# POWER.net
KiCad netlist of a schematic drawn in Altium Designer
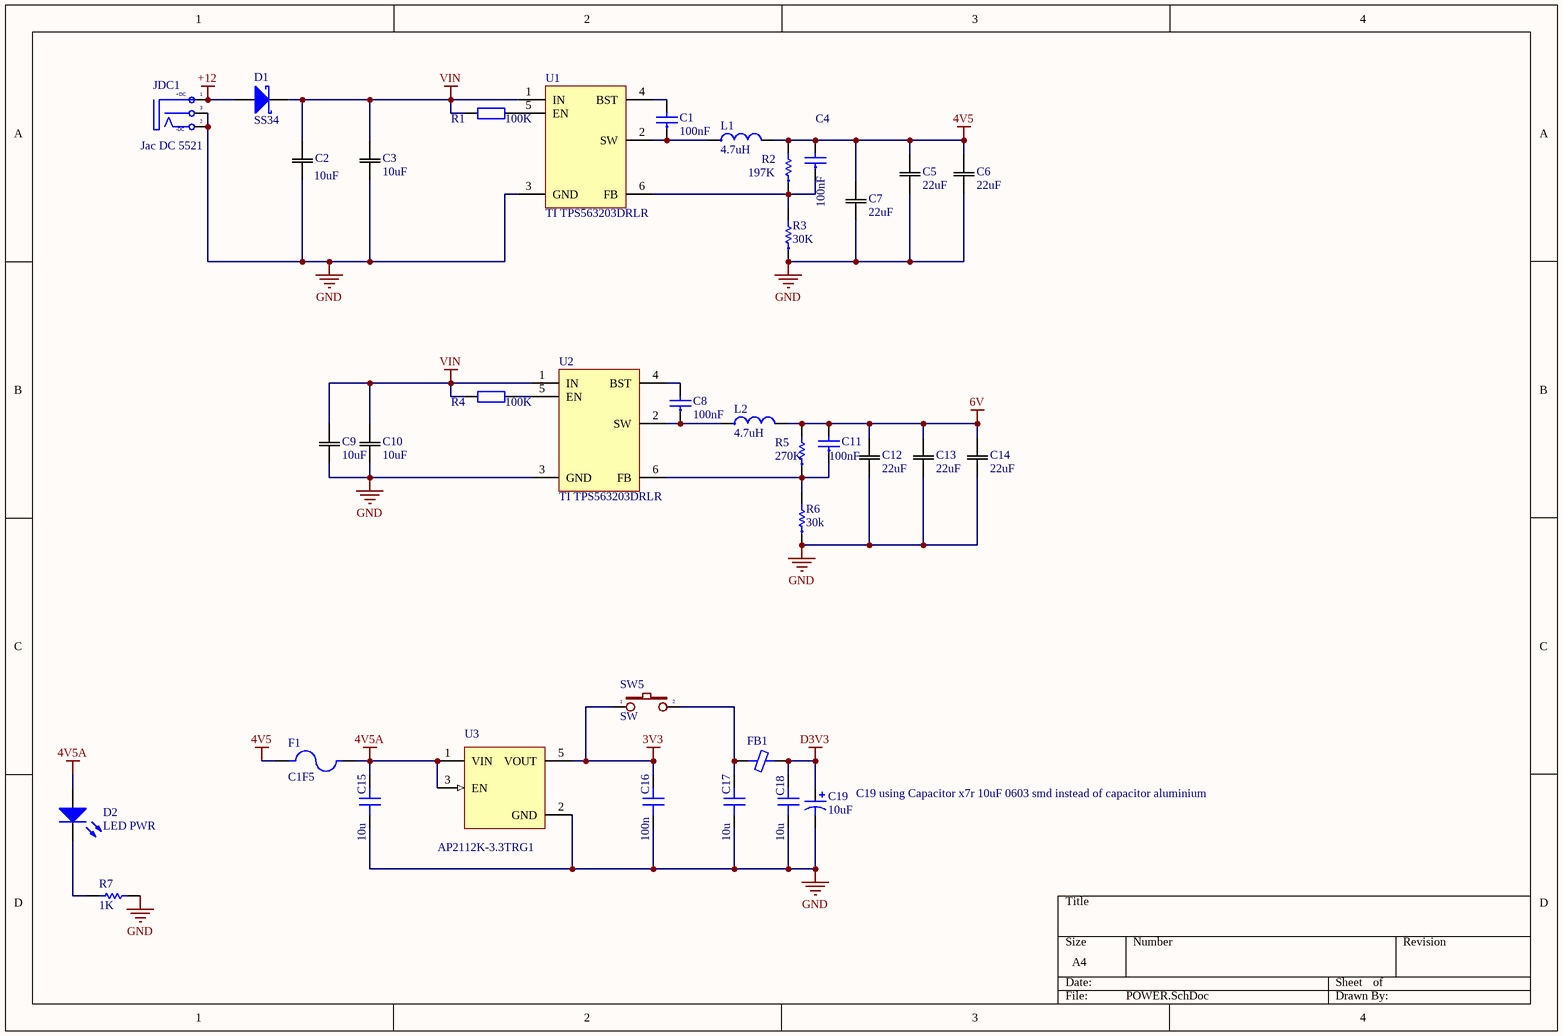
[diagram p0: POWER.SchDoc]

(export (version "E")
  (design (tool "Eeschema 10.0.6"))
  (components
    (comp (ref "C1")
      (value "100nF")
      (footprint "CN-SMD-0603")
      (description "CAP CER 100nF 10% 50V X7R 0603 SMD")
      (libsource (lib "2502-GMQLITE-MAIN") (part "CAPCER0001 100nF 10% 50V X7R 0603 SMD_1"))
    )
    (comp (ref "C2")
      (value "10uF")
      (footprint "CL10A106MQ8NNNC:CAP_CL10_SAM")
      (description "Description")
      (fields
        (field (name "MANUFACTURER_PART_NUMBER") "CL10A106MQ8NNNC")
        (field (name "COPYRIGHT") "Copyright (C) 2026 Ultra Librarian. All rights reserved.")
      )
      (libsource (lib "CL10A106MQ8NNNC") (part "CL10A106MQ8NNNC"))
    )
    (comp (ref "C3")
      (value "10uF")
      (footprint "CL10A106MQ8NNNC:CAP_CL10_SAM")
      (description "Description")
      (fields
        (field (name "MANUFACTURER_PART_NUMBER") "CL10A106MQ8NNNC")
        (field (name "COPYRIGHT") "Copyright (C) 2026 Ultra Librarian. All rights reserved.")
      )
      (libsource (lib "CL10A106MQ8NNNC") (part "CL10A106MQ8NNNC"))
    )
    (comp (ref "C4")
      (value "100nF")
      (footprint "CN-SMD-0603")
      (description "CAP CER 100nF 10% 50V X7R 0603 SMD")
      (libsource (lib "2502-GMQLITE-MAIN") (part "CAPCER0001 100nF 10% 50V X7R 0603 SMD"))
    )
    (comp (ref "C5")
      (value "22uF")
      (footprint "CN-SMD-0603")
      (description "Description")
      (fields
        (field (name "MANUFACTURER_PART_NUMBER") "GRM188R60J226MEA0D")
        (field (name "COPYRIGHT") "Copyright (C) 2026 Ultra Librarian. All rights reserved.")
      )
      (libsource (lib "GRM188R60J226MEA0D") (part "GRM188R60J226MEA0D"))
    )
    (comp (ref "C6")
      (value "22uF")
      (footprint "CN-SMD-0603")
      (description "Description")
      (fields
        (field (name "MANUFACTURER_PART_NUMBER") "GRM188R60J226MEA0D")
        (field (name "COPYRIGHT") "Copyright (C) 2026 Ultra Librarian. All rights reserved.")
      )
      (libsource (lib "GRM188R60J226MEA0D") (part "GRM188R60J226MEA0D"))
    )
    (comp (ref "C7")
      (value "22uF")
      (footprint "CN-SMD-0603")
      (description "Description")
      (fields
        (field (name "MANUFACTURER_PART_NUMBER") "GRM188R60J226MEA0D")
        (field (name "COPYRIGHT") "Copyright (C) 2026 Ultra Librarian. All rights reserved.")
      )
      (libsource (lib "GRM188R60J226MEA0D") (part "GRM188R60J226MEA0D"))
    )
    (comp (ref "C8")
      (value "100nF")
      (footprint "CN-SMD-0603")
      (description "CAP CER 100nF 10% 50V X7R 0603 SMD")
      (libsource (lib "2502-GMQLITE-MAIN") (part "CAPCER0001 100nF 10% 50V X7R 0603 SMD_1"))
    )
    (comp (ref "C9")
      (value "10uF")
      (footprint "CL10A106MQ8NNNC:CAP_CL10_SAM")
      (description "Description")
      (fields
        (field (name "MANUFACTURER_PART_NUMBER") "CL10A106MQ8NNNC")
        (field (name "COPYRIGHT") "Copyright (C) 2026 Ultra Librarian. All rights reserved.")
      )
      (libsource (lib "CL10A106MQ8NNNC") (part "CL10A106MQ8NNNC"))
    )
    (comp (ref "C10")
      (value "10uF")
      (footprint "CL10A106MQ8NNNC:CAP_CL10_SAM")
      (description "Description")
      (fields
        (field (name "MANUFACTURER_PART_NUMBER") "CL10A106MQ8NNNC")
        (field (name "COPYRIGHT") "Copyright (C) 2026 Ultra Librarian. All rights reserved.")
      )
      (libsource (lib "CL10A106MQ8NNNC") (part "CL10A106MQ8NNNC"))
    )
    (comp (ref "C11")
      (value "100nF")
      (footprint "CN-SMD-0603")
      (description "CAP CER 100nF 10% 50V X7R 0603 SMD")
      (libsource (lib "2502-GMQLITE-MAIN") (part "CAPCER0001 100nF 10% 50V X7R 0603 SMD"))
    )
    (comp (ref "C12")
      (value "22uF")
      (footprint "CN-SMD-0603")
      (description "Description")
      (fields
        (field (name "MANUFACTURER_PART_NUMBER") "GRM188R60J226MEA0D")
        (field (name "COPYRIGHT") "Copyright (C) 2026 Ultra Librarian. All rights reserved.")
      )
      (libsource (lib "GRM188R60J226MEA0D") (part "GRM188R60J226MEA0D"))
    )
    (comp (ref "C13")
      (value "22uF")
      (footprint "CN-SMD-0603")
      (description "Description")
      (fields
        (field (name "MANUFACTURER_PART_NUMBER") "GRM188R60J226MEA0D")
        (field (name "COPYRIGHT") "Copyright (C) 2026 Ultra Librarian. All rights reserved.")
      )
      (libsource (lib "GRM188R60J226MEA0D") (part "GRM188R60J226MEA0D"))
    )
    (comp (ref "C14")
      (value "22uF")
      (footprint "CN-SMD-0603")
      (description "Description")
      (fields
        (field (name "MANUFACTURER_PART_NUMBER") "GRM188R60J226MEA0D")
        (field (name "COPYRIGHT") "Copyright (C) 2026 Ultra Librarian. All rights reserved.")
      )
      (libsource (lib "GRM188R60J226MEA0D") (part "GRM188R60J226MEA0D"))
    )
    (comp (ref "C15")
      (value "10u")
      (footprint "CN-SMD-0603")
      (description "CAP0603 X7R 10UF 10% 10V")
      (fields
        (field (name "PART NUMBER") "GMC10X7R106K10NT")
        (field (name "MANUFACTURER") "Cal-Chip Electronics, Inc.")
      )
      (libsource (lib "Celestial Altium Library - altium_library") (part "Capacitor"))
    )
    (comp (ref "C16")
      (value "100n")
      (footprint "CN-SMD-0603")
      (description "CAP0603 X7R 100nF 10% 10V")
      (fields
        (field (name "PART NUMBER") "GMC10X7R106K10NT")
        (field (name "MANUFACTURER") "Cal-Chip Electronics, Inc.")
      )
      (libsource (lib "Celestial Altium Library - altium_library") (part "Capacitor"))
    )
    (comp (ref "C17")
      (value "10u")
      (footprint "CN-SMD-0603")
      (description "CAP0603 X7R 10UF 10% 10V")
      (fields
        (field (name "PART NUMBER") "GMC10X7R106K10NT")
        (field (name "MANUFACTURER") "Cal-Chip Electronics, Inc.")
      )
      (libsource (lib "Celestial Altium Library - altium_library") (part "Capacitor"))
    )
    (comp (ref "C18")
      (value "10u")
      (footprint "CN-SMD-0603")
      (description "CAP0603 X7R 10UF 10% 10V")
      (fields
        (field (name "PART NUMBER") "GMC10X7R106K10NT")
        (field (name "MANUFACTURER") "Cal-Chip Electronics, Inc.")
      )
      (libsource (lib "Celestial Altium Library - altium_library") (part "Capacitor"))
    )
    (comp (ref "C19")
      (value "10uF")
      (footprint "CN-SMD-0603")
      (description "CAP ALUM 100UF 20% \r\n16V SMD")
      (fields (field (name "Comment") "CAP ALUM 100UF 20% 16V SMD"))
      (libsource (lib "capacitor") (part "UWT1C101MCL1GB"))
    )
    (comp (ref "D1")
      (value "SS34")
      (footprint "DIO-SMD-106")
      (description "Schottky Diode 40V 3A SMA")
      (libsource (lib "diode") (part "SS34"))
    )
    (comp (ref "D2")
      (value "LED PWR")
      (footprint "LED-0805-Red")
      (description "Lite-On LED Red 0603")
      (fields (field (name "Comment") "LED Red"))
      (libsource (lib "diode") (part "LTST-C190KRKT"))
    )
    (comp (ref "F1")
      (value "C1F5")
      (footprint "RES-SMD-1206")
      (description "Fuse Chip Fast Acting 5A 125V SMD Solder Pad 1206 3.2 X 1.58 X 0.63mm")
      (fields (field (name "MANUFACTURER") "Bel TRP"))
      (libsource (lib "POWER_PIN_CAMERA") (part "C1F5"))
    )
    (comp (ref "FB1")
      (value "330")
      (footprint "IND_BLM18KG331WH1D_MUR-L")
      (description "FERRITE BEAD 330 OHM 0603 1LN")
      (fields
        (field (name "PART NUMBER") "BLM18KG331SH1D")
        (field (name "MANUFACTURER") "Murata Electronics")
      )
      (libsource (lib "Celestial Altium Library - altium_library") (part "Ferrite Chip"))
    )
    (comp (ref "JDC1")
      (value "Jac DC 5521")
      (footprint "DC0")
      (description "Jac DC input")
      (libsource (lib "2502-GMQLITE-MAIN") (part "DCIN"))
    )
    (comp (ref "L1")
      (value "4.7uH")
      (footprint "Inductor_SMD")
      (description "IND MOI 1W2T 4.7uH 20% 5A 0420 SMD")
      (libsource (lib "2502-GMQLITE-MAIN") (part "INDMOI0016 1W2T 2.2uH 20% 5A 0420 SMD"))
    )
    (comp (ref "L2")
      (value "4.7uH")
      (footprint "Inductor_SMD")
      (description "IND MOI 1W2T 4.7uH 20% 5A 0420 SMD")
      (libsource (lib "2502-GMQLITE-MAIN") (part "INDMOI0016 1W2T 2.2uH 20% 5A 0420 SMD"))
    )
    (comp (ref "R1")
      (value "100K")
      (footprint "RES-SMD-0603")
      (description "Yageo RES 100K 5% 1/10W 0603")
      (fields (field (name "Comment") "RES 100K 5% 1/10W 0603"))
      (libsource (lib "resistor") (part "RC0603JR-07100KL"))
    )
    (comp (ref "R2")
      (value "197K")
      (footprint "RES-SMD-0603")
      (description "RES CHP 2K7 1% 1/10W 0603 SMD")
      (libsource (lib "2502-GMQLITE-MAIN") (part "RESCHP0195 2K7 1% 0603 SMD"))
    )
    (comp (ref "R3")
      (value "30K")
      (footprint "RES-SMD-0603")
      (description "RES CHP 2K7 1% 1/10W 0603 SMD")
      (libsource (lib "2502-GMQLITE-MAIN") (part "RESCHP0195 2K7 1% 0603 SMD"))
    )
    (comp (ref "R4")
      (value "100K")
      (footprint "RES-SMD-0603")
      (description "Yageo RES 100K 5% 1/10W 0603")
      (fields (field (name "Comment") "RES 100K 5% 1/10W 0603"))
      (libsource (lib "resistor") (part "RC0603JR-07100KL"))
    )
    (comp (ref "R5")
      (value "270K")
      (footprint "RES-SMD-0603")
      (description "RES CHP 2K7 1% 1/10W 0603 SMD")
      (libsource (lib "2502-GMQLITE-MAIN") (part "RESCHP0195 2K7 1% 0603 SMD"))
    )
    (comp (ref "R6")
      (value "30k")
      (footprint "RES-SMD-0603")
      (description "RES CHP 2K7 1% 1/10W 0603 SMD")
      (libsource (lib "2502-GMQLITE-MAIN") (part "RESCHP0195 2K7 1% 0603 SMD"))
    )
    (comp (ref "R7")
      (value "1K")
      (footprint "RES-SMD-0603")
      (description "Res Thick Film 0603 2.2K Ohm 5% 1/10W ±200ppm/°C Molded SMD SMD Paper T/R")
      (fields
        (field (name "MANUFACTURER") "Vishay")
        (field (name "MANUFACTURER PART NUMBER") "CRCW06032K20JNEA")
      )
      (libsource (lib "Stm32_Flyback_Driver_250814_1") (part "Resistor 2.2K"))
    )
    (comp (ref "SW5")
      (value "SW")
      (footprint "SW-DIP1")
      (description "Switch button 2 pin")
      (libsource (lib "Altium Library") (part "SW2"))
    )
    (comp (ref "U1")
      (value "TI TPS563203DRLR")
      (footprint "SOT_07SDRLR_TEX")
      (description "ICS OCV BCK TPS563201 3A SOT23-6 SMD")
      (libsource (lib "2502-GMQLITE-MAIN") (part "ICSOCV0021 BCK TPS563201 3A SOT23-6 SMD"))
    )
    (comp (ref "U2")
      (value "TI TPS563203DRLR")
      (footprint "SOT_07SDRLR_TEX")
      (description "ICS OCV BCK TPS563201 3A SOT23-6 SMD")
      (libsource (lib "2502-GMQLITE-MAIN") (part "ICSOCV0021 BCK TPS563201 3A SOT23-6 SMD"))
    )
    (comp (ref "U3")
      (value "AP2112K-3.3TRG1")
      (footprint "AP2112K-3P3TRG1:SOT_RG1_DIO")
      (description "AP2112 Series 0.6 A 3.3 V Fixed Output SMT LDO Linear Regulator - SOT23-5")
      (fields (field (name "MF") "Diodes Inc."))
      (libsource (lib "hanguyen") (part "AP2112K-3.3TRG1"))
    )
  )
  (nets
    (net (code "1") (name "+12") (class "Default")
      (node (ref "D1") (pin "1") (pinfunction "A_1") (pintype "passive"))
      (node (ref "JDC1") (pin "1") (pinfunction "T_1") (pintype "passive"))
    )
    (net (code "2") (name "3V3") (class "Default")
      (node (ref "C16") (pin "2") (pinfunction "2_2") (pintype "passive"))
      (node (ref "SW5") (pin "1") (pinfunction "1_1") (pintype "passive"))
      (node (ref "U3") (pin "5") (pinfunction "VOUT_5") (pintype "power_in"))
    )
    (net (code "3") (name "4V5") (class "Default")
      (node (ref "C4") (pin "2") (pinfunction "2_2") (pintype "passive"))
      (node (ref "C5") (pin "2") (pinfunction "2_2") (pintype "passive"))
      (node (ref "C6") (pin "2") (pinfunction "2_2") (pintype "passive"))
      (node (ref "C7") (pin "2") (pinfunction "2_2") (pintype "passive"))
      (node (ref "F1") (pin "1") (pinfunction "1_1") (pintype "passive"))
      (node (ref "L1") (pin "2") (pinfunction "2_2") (pintype "passive"))
      (node (ref "R2") (pin "2") (pinfunction "2_2") (pintype "passive"))
    )
    (net (code "4") (name "4V5A") (class "Default")
      (node (ref "C15") (pin "2") (pinfunction "2_2") (pintype "passive"))
      (node (ref "D2") (pin "1") (pinfunction "A_1") (pintype "passive"))
      (node (ref "F1") (pin "2") (pinfunction "2_2") (pintype "passive"))
      (node (ref "U3") (pin "1") (pinfunction "VIN_1") (pintype "power_in"))
      (node (ref "U3") (pin "3") (pinfunction "EN_3") (pintype "input"))
    )
    (net (code "5") (name "6V") (class "Default")
      (node (ref "C11") (pin "2") (pinfunction "2_2") (pintype "passive"))
      (node (ref "C12") (pin "2") (pinfunction "2_2") (pintype "passive"))
      (node (ref "C13") (pin "2") (pinfunction "2_2") (pintype "passive"))
      (node (ref "C14") (pin "2") (pinfunction "2_2") (pintype "passive"))
      (node (ref "L2") (pin "2") (pinfunction "2_2") (pintype "passive"))
      (node (ref "R5") (pin "2") (pinfunction "2_2") (pintype "passive"))
    )
    (net (code "6") (name "D3V3") (class "Default")
      (node (ref "C18") (pin "2") (pinfunction "2_2") (pintype "passive"))
      (node (ref "C19") (pin "1") (pinfunction "1_1") (pintype "passive"))
      (node (ref "FB1") (pin "2") (pinfunction "2_2") (pintype "passive"))
    )
    (net (code "7") (name "GND") (class "Default")
      (node (ref "C10") (pin "1") (pinfunction "1_1") (pintype "passive"))
      (node (ref "C12") (pin "1") (pinfunction "1_1") (pintype "passive"))
      (node (ref "C13") (pin "1") (pinfunction "1_1") (pintype "passive"))
      (node (ref "C14") (pin "1") (pinfunction "1_1") (pintype "passive"))
      (node (ref "C15") (pin "1") (pinfunction "1_1") (pintype "passive"))
      (node (ref "C16") (pin "1") (pinfunction "1_1") (pintype "passive"))
      (node (ref "C17") (pin "1") (pinfunction "1_1") (pintype "passive"))
      (node (ref "C18") (pin "1") (pinfunction "1_1") (pintype "passive"))
      (node (ref "C19") (pin "2") (pinfunction "2_2") (pintype "passive"))
      (node (ref "C2") (pin "1") (pinfunction "1_1") (pintype "passive"))
      (node (ref "C3") (pin "1") (pinfunction "1_1") (pintype "passive"))
      (node (ref "C5") (pin "1") (pinfunction "1_1") (pintype "passive"))
      (node (ref "C6") (pin "1") (pinfunction "1_1") (pintype "passive"))
      (node (ref "C7") (pin "1") (pinfunction "1_1") (pintype "passive"))
      (node (ref "C9") (pin "1") (pinfunction "1_1") (pintype "passive"))
      (node (ref "JDC1") (pin "2") (pinfunction "TN_2") (pintype "passive"))
      (node (ref "JDC1") (pin "3") (pinfunction "S_3") (pintype "power_in"))
      (node (ref "R3") (pin "1") (pinfunction "1_1") (pintype "passive"))
      (node (ref "R6") (pin "1") (pinfunction "1_1") (pintype "passive"))
      (node (ref "R7") (pin "2") (pinfunction "2_2") (pintype "passive"))
      (node (ref "U1") (pin "3") (pinfunction "GND_3") (pintype "power_in"))
      (node (ref "U2") (pin "3") (pinfunction "GND_3") (pintype "power_in"))
      (node (ref "U3") (pin "2") (pinfunction "GND_2") (pintype "power_in"))
    )
    (net (code "8") (name "Net-(C17-Pad2)") (class "Default")
      (node (ref "C17") (pin "2") (pinfunction "2_2") (pintype "passive"))
      (node (ref "FB1") (pin "1") (pinfunction "1_1") (pintype "passive"))
      (node (ref "SW5") (pin "2") (pinfunction "2_2") (pintype "passive"))
    )
    (net (code "9") (name "Net-(D2-K)") (class "Default")
      (node (ref "D2") (pin "2") (pinfunction "K_2") (pintype "passive"))
      (node (ref "R7") (pin "1") (pinfunction "1_1") (pintype "passive"))
    )
    (net (code "10") (name "Net-(U1-BST)") (class "Default")
      (node (ref "C1") (pin "2") (pinfunction "2_2") (pintype "passive"))
      (node (ref "U1") (pin "4") (pinfunction "BST_4") (pintype "passive"))
    )
    (net (code "11") (name "Net-(U1-EN)") (class "Default")
      (node (ref "R1") (pin "1") (pinfunction "1_1") (pintype "passive"))
      (node (ref "U1") (pin "5") (pinfunction "EN_5") (pintype "passive"))
    )
    (net (code "12") (name "Net-(U1-FB)") (class "Default")
      (node (ref "C4") (pin "1") (pinfunction "1_1") (pintype "passive"))
      (node (ref "R2") (pin "1") (pinfunction "1_1") (pintype "passive"))
      (node (ref "R3") (pin "2") (pinfunction "2_2") (pintype "passive"))
      (node (ref "U1") (pin "6") (pinfunction "FB_6") (pintype "passive"))
    )
    (net (code "13") (name "Net-(U1-SW)") (class "Default")
      (node (ref "C1") (pin "1") (pinfunction "1_1") (pintype "passive"))
      (node (ref "L1") (pin "1") (pinfunction "1_1") (pintype "passive"))
      (node (ref "U1") (pin "2") (pinfunction "SW_2") (pintype "passive"))
    )
    (net (code "14") (name "Net-(U2-BST)") (class "Default")
      (node (ref "C8") (pin "2") (pinfunction "2_2") (pintype "passive"))
      (node (ref "U2") (pin "4") (pinfunction "BST_4") (pintype "passive"))
    )
    (net (code "15") (name "Net-(U2-EN)") (class "Default")
      (node (ref "R4") (pin "1") (pinfunction "1_1") (pintype "passive"))
      (node (ref "U2") (pin "5") (pinfunction "EN_5") (pintype "passive"))
    )
    (net (code "16") (name "Net-(U2-FB)") (class "Default")
      (node (ref "C11") (pin "1") (pinfunction "1_1") (pintype "passive"))
      (node (ref "R5") (pin "1") (pinfunction "1_1") (pintype "passive"))
      (node (ref "R6") (pin "2") (pinfunction "2_2") (pintype "passive"))
      (node (ref "U2") (pin "6") (pinfunction "FB_6") (pintype "passive"))
    )
    (net (code "17") (name "Net-(U2-SW)") (class "Default")
      (node (ref "C8") (pin "1") (pinfunction "1_1") (pintype "passive"))
      (node (ref "L2") (pin "1") (pinfunction "1_1") (pintype "passive"))
      (node (ref "U2") (pin "2") (pinfunction "SW_2") (pintype "passive"))
    )
    (net (code "18") (name "VIN") (class "Default")
      (node (ref "C10") (pin "2") (pinfunction "2_2") (pintype "passive"))
      (node (ref "C2") (pin "2") (pinfunction "2_2") (pintype "passive"))
      (node (ref "C3") (pin "2") (pinfunction "2_2") (pintype "passive"))
      (node (ref "C9") (pin "2") (pinfunction "2_2") (pintype "passive"))
      (node (ref "D1") (pin "2") (pinfunction "K_2") (pintype "passive"))
      (node (ref "R1") (pin "2") (pinfunction "2_2") (pintype "passive"))
      (node (ref "R4") (pin "2") (pinfunction "2_2") (pintype "passive"))
      (node (ref "U1") (pin "1") (pinfunction "IN_1") (pintype "power_in"))
      (node (ref "U2") (pin "1") (pinfunction "IN_1") (pintype "power_in"))
    )
  )
)
